# ADS1015_12Bit_I2C_ADC_v0_2.net
KiCad netlist of a schematic drawn in EAGLE
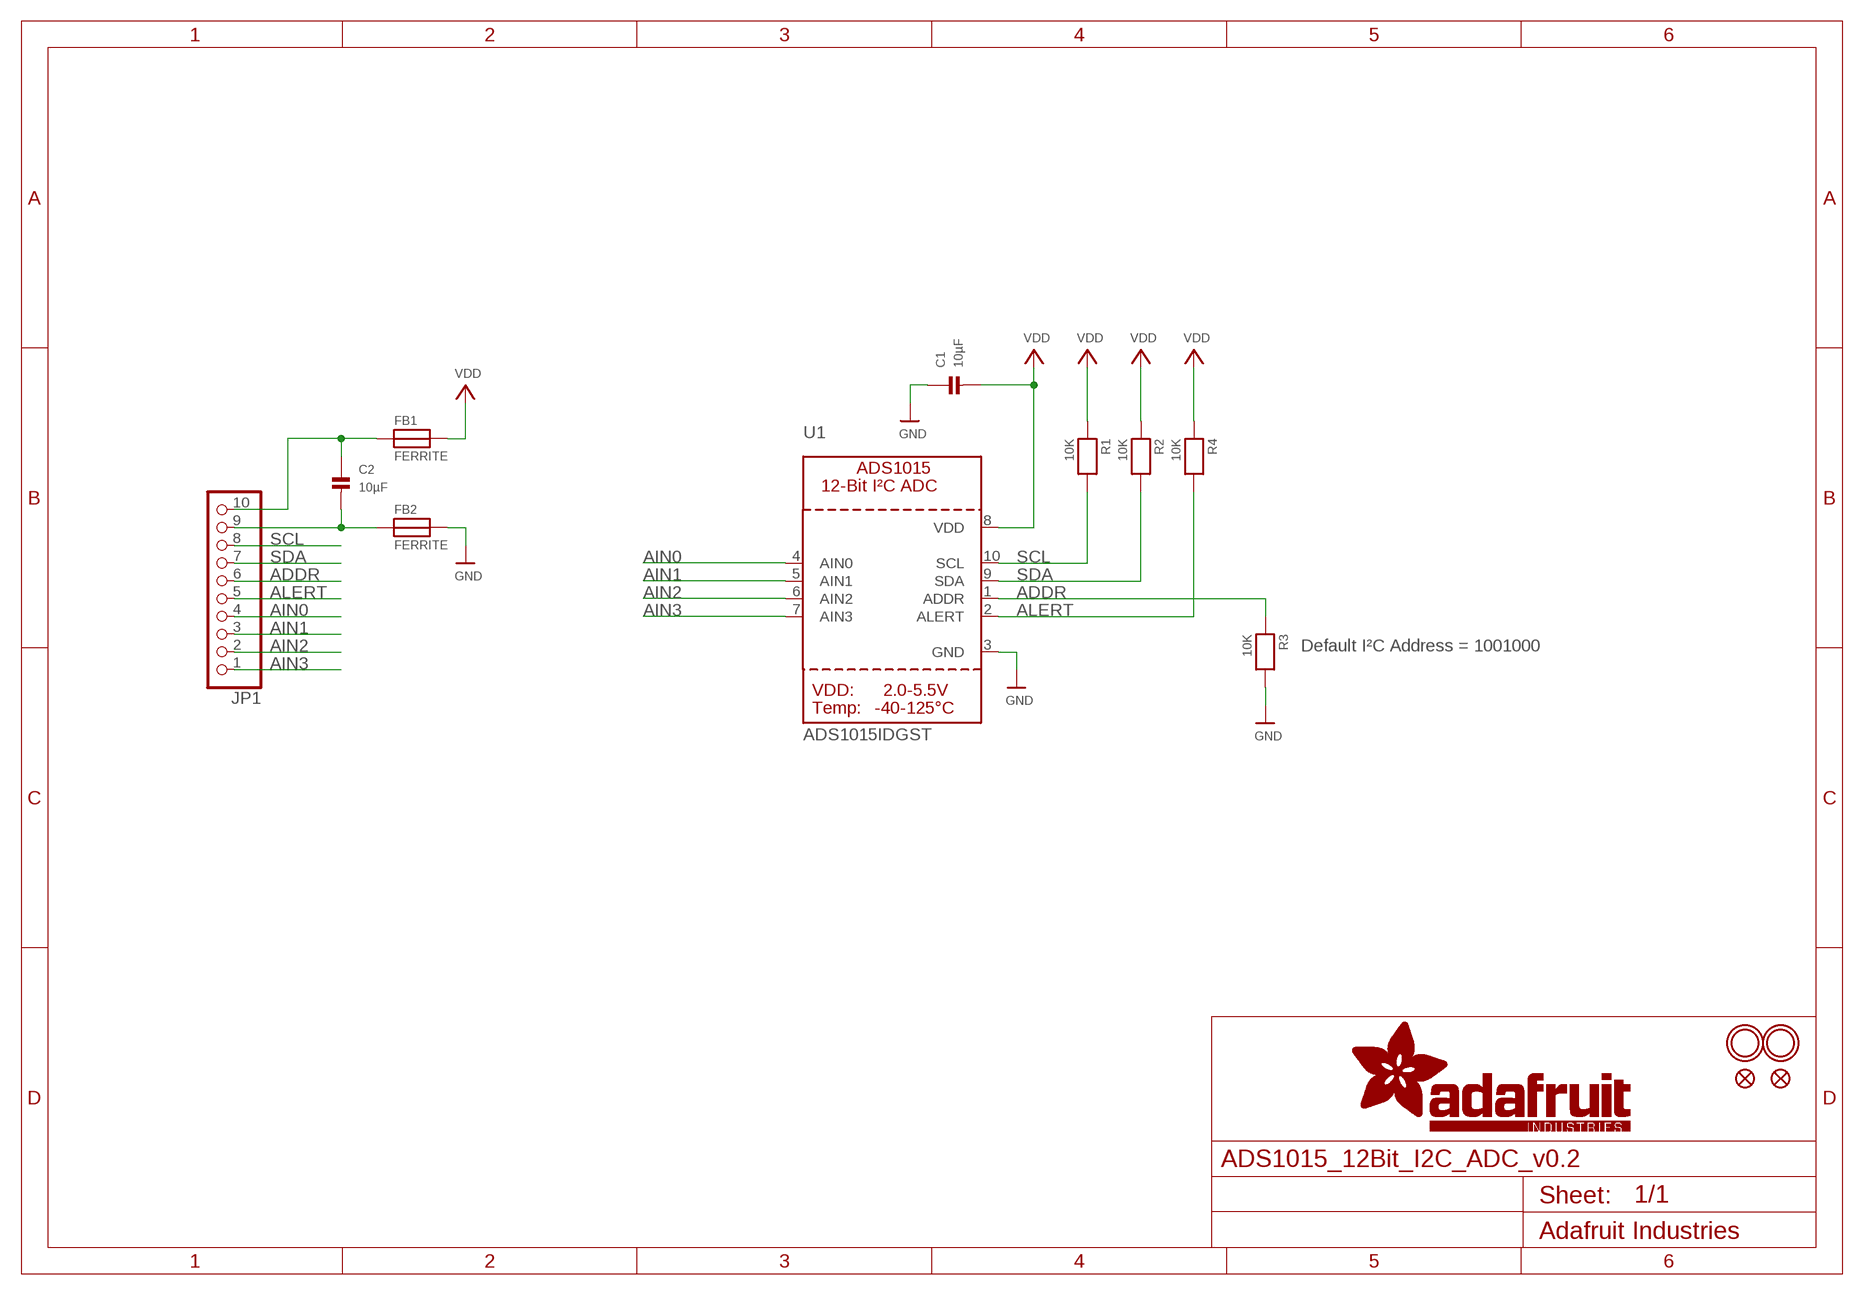
[diagram p0: schematic, sheet 1]

(export (version "E")
  (design (tool "Eeschema 10.0.6"))
  (components
    (comp (ref "C1")
      (value "10µF")
      (footprint "eagle-import:0805")
      (libsource (lib "eagle-import") (part "CAP_CERAMIC0805"))
    )
    (comp (ref "C2")
      (value "10µF")
      (footprint "eagle-import:0805")
      (libsource (lib "eagle-import") (part "CAP_CERAMIC0805"))
    )
    (comp (ref "FB1")
      (value "FERRITE")
      (footprint "eagle-import:0805")
      (libsource (lib "eagle-import") (part "FERRITE0805"))
    )
    (comp (ref "FB2")
      (value "FERRITE")
      (footprint "eagle-import:0805")
      (libsource (lib "eagle-import") (part "FERRITE0805"))
    )
    (comp (ref "FID1")
      (value "FIDUCIAL\"\"")
      (footprint "eagle-import:FIDUCIAL_1MM")
      (libsource (lib "eagle-import") (part "FIDUCIAL{dblquote}{dblquote}"))
    )
    (comp (ref "FID2")
      (value "FIDUCIAL\"\"")
      (footprint "eagle-import:FIDUCIAL_1MM")
      (libsource (lib "eagle-import") (part "FIDUCIAL{dblquote}{dblquote}"))
    )
    (comp (ref "JP1")
      (value "HEADER-1X1070MIL")
      (footprint "eagle-import:1X10_ROUND70")
      (libsource (lib "eagle-import") (part "HEADER-1X1070MIL"))
    )
    (comp (ref "R1")
      (value "10K")
      (footprint "eagle-import:0805")
      (libsource (lib "eagle-import") (part "RESISTOR0805"))
    )
    (comp (ref "R2")
      (value "10K")
      (footprint "eagle-import:0805")
      (libsource (lib "eagle-import") (part "RESISTOR0805"))
    )
    (comp (ref "R3")
      (value "10K")
      (footprint "eagle-import:0805")
      (libsource (lib "eagle-import") (part "RESISTOR0805"))
    )
    (comp (ref "R4")
      (value "10K")
      (footprint "eagle-import:0805")
      (libsource (lib "eagle-import") (part "RESISTOR0805"))
    )
    (comp (ref "U$13")
      (value "MOUNTINGHOLE2.5")
      (footprint "eagle-import:MOUNTINGHOLE_2.5_PLATED")
      (libsource (lib "eagle-import") (part "MOUNTINGHOLE2.5"))
    )
    (comp (ref "U$14")
      (value "MOUNTINGHOLE2.5")
      (footprint "eagle-import:MOUNTINGHOLE_2.5_PLATED")
      (libsource (lib "eagle-import") (part "MOUNTINGHOLE2.5"))
    )
    (comp (ref "U1")
      (value "ADS1015IDGST")
      (footprint "eagle-import:MSOP10")
      (libsource (lib "eagle-import") (part "ADC_ADS1015"))
    )
  )
  (nets
    (net (code "1") (name "/ADDR") (class "Default")
      (node (ref "JP1") (pin "6") (pinfunction "6_6") (pintype "passive"))
      (node (ref "R3") (pin "1") (pinfunction "1_1") (pintype "passive"))
      (node (ref "U1") (pin "1") (pinfunction "ADDR_1") (pintype "bidirectional"))
    )
    (net (code "2") (name "/AIN0") (class "Default")
      (node (ref "JP1") (pin "4") (pinfunction "4_4") (pintype "passive"))
      (node (ref "U1") (pin "4") (pinfunction "AIN0_4") (pintype "bidirectional"))
    )
    (net (code "3") (name "/AIN1") (class "Default")
      (node (ref "JP1") (pin "3") (pinfunction "3_3") (pintype "passive"))
      (node (ref "U1") (pin "5") (pinfunction "AIN1_5") (pintype "bidirectional"))
    )
    (net (code "4") (name "/AIN2") (class "Default")
      (node (ref "JP1") (pin "2") (pinfunction "2_2") (pintype "passive"))
      (node (ref "U1") (pin "6") (pinfunction "AIN2_6") (pintype "bidirectional"))
    )
    (net (code "5") (name "/AIN3") (class "Default")
      (node (ref "JP1") (pin "1") (pinfunction "1_1") (pintype "passive"))
      (node (ref "U1") (pin "7") (pinfunction "AIN3_7") (pintype "bidirectional"))
    )
    (net (code "6") (name "/ALERT") (class "Default")
      (node (ref "JP1") (pin "5") (pinfunction "5_5") (pintype "passive"))
      (node (ref "R4") (pin "2") (pinfunction "2_2") (pintype "passive"))
      (node (ref "U1") (pin "2") (pinfunction "ALERT_2") (pintype "bidirectional"))
    )
    (net (code "7") (name "/SCL") (class "Default")
      (node (ref "JP1") (pin "8") (pinfunction "8_8") (pintype "passive"))
      (node (ref "R1") (pin "2") (pinfunction "2_2") (pintype "passive"))
      (node (ref "U1") (pin "10") (pinfunction "SCL_10") (pintype "bidirectional"))
    )
    (net (code "8") (name "/SDA") (class "Default")
      (node (ref "JP1") (pin "7") (pinfunction "7_7") (pintype "passive"))
      (node (ref "R2") (pin "2") (pinfunction "2_2") (pintype "passive"))
      (node (ref "U1") (pin "9") (pinfunction "SDA_9") (pintype "bidirectional"))
    )
    (net (code "9") (name "GND") (class "Default")
      (node (ref "C1") (pin "1") (pinfunction "P$1_1") (pintype "passive"))
      (node (ref "FB2") (pin "2") (pinfunction "P$2_2") (pintype "bidirectional"))
      (node (ref "R3") (pin "2") (pinfunction "2_2") (pintype "passive"))
      (node (ref "U1") (pin "3") (pinfunction "GND_3") (pintype "bidirectional"))
    )
    (net (code "10") (name "Net-(C2-P$1)") (class "Default")
      (node (ref "C2") (pin "1") (pinfunction "P$1_1") (pintype "passive"))
      (node (ref "FB1") (pin "1") (pinfunction "P$1_1") (pintype "bidirectional"))
      (node (ref "JP1") (pin "10") (pinfunction "10_10") (pintype "passive"))
    )
    (net (code "11") (name "Net-(C2-P$2)") (class "Default")
      (node (ref "C2") (pin "2") (pinfunction "P$2_2") (pintype "passive"))
      (node (ref "FB2") (pin "1") (pinfunction "P$1_1") (pintype "bidirectional"))
      (node (ref "JP1") (pin "9") (pinfunction "9_9") (pintype "passive"))
    )
    (net (code "12") (name "VDD") (class "Default")
      (node (ref "C1") (pin "2") (pinfunction "P$2_2") (pintype "passive"))
      (node (ref "FB1") (pin "2") (pinfunction "P$2_2") (pintype "bidirectional"))
      (node (ref "R1") (pin "1") (pinfunction "1_1") (pintype "passive"))
      (node (ref "R2") (pin "1") (pinfunction "1_1") (pintype "passive"))
      (node (ref "R4") (pin "1") (pinfunction "1_1") (pintype "passive"))
      (node (ref "U1") (pin "8") (pinfunction "VDD_8") (pintype "bidirectional"))
    )
  )
)
